# 0116-class-d-amp.net
KiCad netlist of a schematic drawn in EAGLE
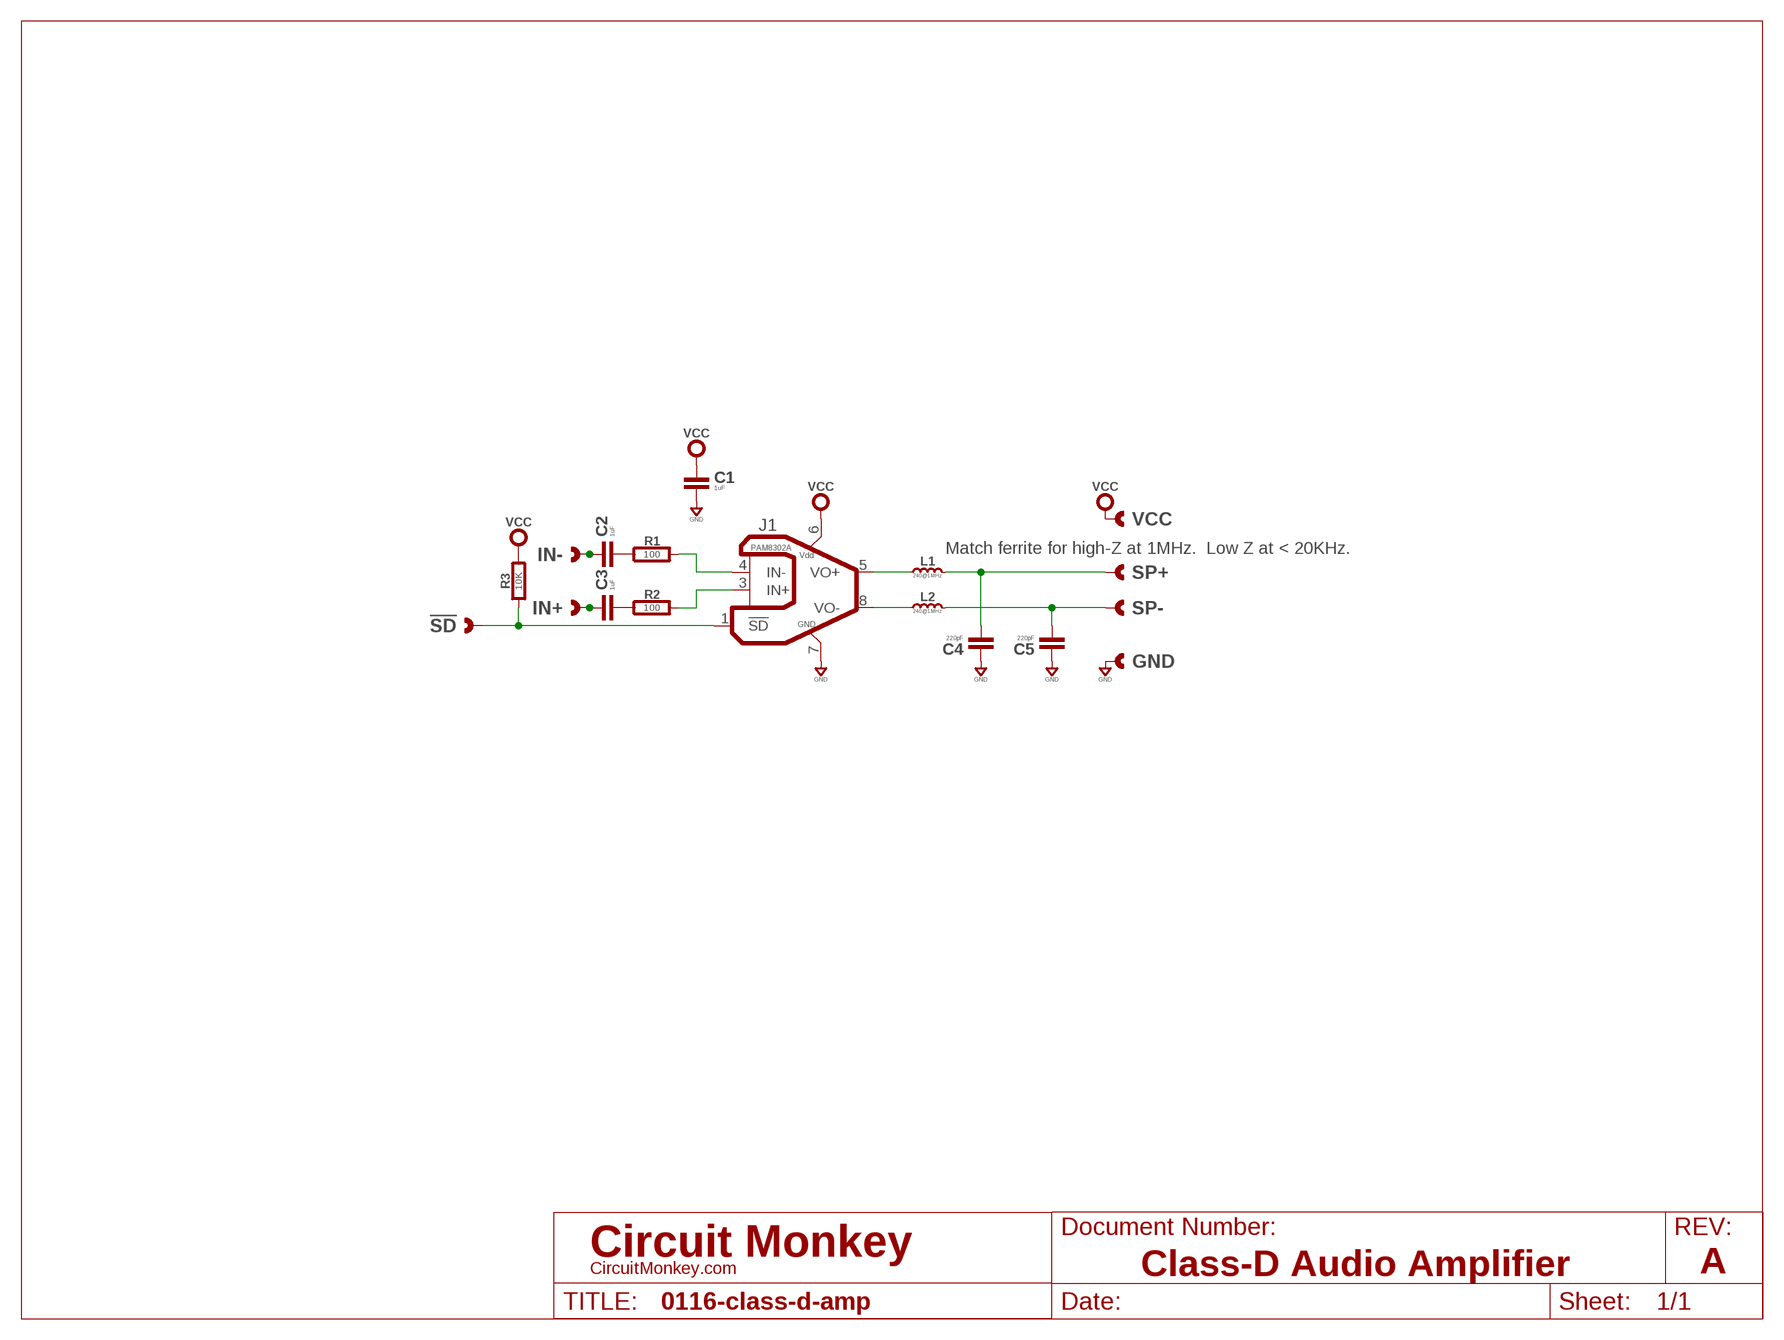
[diagram p0: schematic, sheet 1]

(export (version "E")
  (design (tool "Eeschema 10.0.6"))
  (components
    (comp (ref "!SD")
      (value "CAST-01X12.00MM")
      (footprint "eagle-import:CAST01-2.00MM")
      (libsource (lib "eagle-import") (part "CAST-01X12.00MM"))
    )
    (comp (ref "C1")
      (value "1uF")
      (footprint "eagle-import:0402-CAP")
      (libsource (lib "eagle-import") (part "CAPACITOR0402"))
    )
    (comp (ref "C2")
      (value "1uF")
      (footprint "eagle-import:0402-CAP")
      (libsource (lib "eagle-import") (part "CAPACITOR0402"))
    )
    (comp (ref "C3")
      (value "1uF")
      (footprint "eagle-import:0402-CAP")
      (libsource (lib "eagle-import") (part "CAPACITOR0402"))
    )
    (comp (ref "C4")
      (value "220pF")
      (footprint "eagle-import:0402-CAP")
      (libsource (lib "eagle-import") (part "CAPACITOR0402"))
    )
    (comp (ref "C5")
      (value "220pF")
      (footprint "eagle-import:0402-CAP")
      (libsource (lib "eagle-import") (part "CAPACITOR0402"))
    )
    (comp (ref "GND")
      (value "CAST-01X12.00MM")
      (footprint "eagle-import:CAST01-2.00MM")
      (libsource (lib "eagle-import") (part "CAST-01X12.00MM"))
    )
    (comp (ref "IN+")
      (value "CAST-01X12.00MM")
      (footprint "eagle-import:CAST01-2.00MM")
      (libsource (lib "eagle-import") (part "CAST-01X12.00MM"))
    )
    (comp (ref "IN-")
      (value "CAST-01X12.00MM")
      (footprint "eagle-import:CAST01-2.00MM")
      (libsource (lib "eagle-import") (part "CAST-01X12.00MM"))
    )
    (comp (ref "J1")
      (value "PAM8302A")
      (footprint "eagle-import:DFN-8-3X3")
      (fields (field (name "MFR") "Diodes, Inc.") (field (name "MPN") "PAM8302AAYC"))
      (libsource (lib "eagle-import") (part "PAM8302ADFN-3X3"))
    )
    (comp (ref "L1")
      (value "240@1MHz")
      (footprint "eagle-import:0402-IND")
      (fields (field (name "MFR") "TDK") (field (name "MPN") "MMZ1005S241HT000"))
      (libsource (lib "eagle-import") (part "FERRITE240OHM-600MA-0402"))
    )
    (comp (ref "L2")
      (value "240@1MHz")
      (footprint "eagle-import:0402-IND")
      (fields (field (name "MFR") "TDK") (field (name "MPN") "MMZ1005S241HT000"))
      (libsource (lib "eagle-import") (part "FERRITE240OHM-600MA-0402"))
    )
    (comp (ref "R1")
      (value "100")
      (footprint "eagle-import:0402-RES")
      (libsource (lib "eagle-import") (part "RESISTOR0402"))
    )
    (comp (ref "R2")
      (value "100")
      (footprint "eagle-import:0402-RES")
      (libsource (lib "eagle-import") (part "RESISTOR0402"))
    )
    (comp (ref "R3")
      (value "10K")
      (footprint "eagle-import:0402-RES")
      (libsource (lib "eagle-import") (part "RESISTOR0402"))
    )
    (comp (ref "SP+")
      (value "CAST-01X12.00MM")
      (footprint "eagle-import:CAST01-2.00MM")
      (libsource (lib "eagle-import") (part "CAST-01X12.00MM"))
    )
    (comp (ref "SP-")
      (value "CAST-01X12.00MM")
      (footprint "eagle-import:CAST01-2.00MM")
      (libsource (lib "eagle-import") (part "CAST-01X12.00MM"))
    )
    (comp (ref "VCC")
      (value "CAST-01X12.00MM")
      (footprint "eagle-import:CAST01-2.00MM")
      (libsource (lib "eagle-import") (part "CAST-01X12.00MM"))
    )
  )
  (nets
    (net (code "1") (name "GND") (class "Default")
      (node (ref "C1") (pin "2") (pinfunction "2_2") (pintype "passive"))
      (node (ref "C4") (pin "1") (pinfunction "1_1") (pintype "passive"))
      (node (ref "C5") (pin "1") (pinfunction "1_1") (pintype "passive"))
      (node (ref "GND") (pin "1") (pinfunction "1_1") (pintype "bidirectional"))
      (node (ref "GND") (pin "P$1") (pinfunction "1_P$1") (pintype "bidirectional"))
      (node (ref "GND") (pin "P$2") (pinfunction "1_P$2") (pintype "bidirectional"))
      (node (ref "J1") (pin "7") (pinfunction "GND_7") (pintype "bidirectional"))
    )
    (net (code "2") (name "Net-(C2-Pad1)") (class "Default")
      (node (ref "C2") (pin "1") (pinfunction "1_1") (pintype "passive"))
      (node (ref "IN-") (pin "1") (pinfunction "1_1") (pintype "bidirectional"))
      (node (ref "IN-") (pin "P$1") (pinfunction "1_P$1") (pintype "bidirectional"))
      (node (ref "IN-") (pin "P$2") (pinfunction "1_P$2") (pintype "bidirectional"))
    )
    (net (code "3") (name "Net-(C2-Pad2)") (class "Default")
      (node (ref "C2") (pin "2") (pinfunction "2_2") (pintype "passive"))
      (node (ref "R1") (pin "1") (pinfunction "1_1") (pintype "passive"))
    )
    (net (code "4") (name "Net-(C3-Pad1)") (class "Default")
      (node (ref "C3") (pin "1") (pinfunction "1_1") (pintype "passive"))
      (node (ref "IN+") (pin "1") (pinfunction "1_1") (pintype "bidirectional"))
      (node (ref "IN+") (pin "P$1") (pinfunction "1_P$1") (pintype "bidirectional"))
      (node (ref "IN+") (pin "P$2") (pinfunction "1_P$2") (pintype "bidirectional"))
    )
    (net (code "5") (name "Net-(C3-Pad2)") (class "Default")
      (node (ref "C3") (pin "2") (pinfunction "2_2") (pintype "passive"))
      (node (ref "R2") (pin "1") (pinfunction "1_1") (pintype "passive"))
    )
    (net (code "6") (name "Net-(J1-IN+)") (class "Default")
      (node (ref "J1") (pin "3") (pinfunction "IN+_3") (pintype "bidirectional"))
      (node (ref "R2") (pin "2") (pinfunction "2_2") (pintype "passive"))
    )
    (net (code "7") (name "Net-(J1-IN-)") (class "Default")
      (node (ref "J1") (pin "4") (pinfunction "IN-_4") (pintype "bidirectional"))
      (node (ref "R1") (pin "2") (pinfunction "2_2") (pintype "passive"))
    )
    (net (code "8") (name "Net-(J1-VO+)") (class "Default")
      (node (ref "J1") (pin "5") (pinfunction "VO+_5") (pintype "bidirectional"))
      (node (ref "L1") (pin "3") (pinfunction "1_3") (pintype "passive"))
    )
    (net (code "9") (name "Net-(J1-VO-)") (class "Default")
      (node (ref "J1") (pin "8") (pinfunction "VO-_8") (pintype "bidirectional"))
      (node (ref "L2") (pin "3") (pinfunction "1_3") (pintype "passive"))
    )
    (net (code "10") (name "Net-(J1-~{SD})") (class "Default")
      (node (ref "!SD") (pin "1") (pinfunction "1_1") (pintype "bidirectional"))
      (node (ref "!SD") (pin "P$1") (pinfunction "1_P$1") (pintype "bidirectional"))
      (node (ref "!SD") (pin "P$2") (pinfunction "1_P$2") (pintype "bidirectional"))
      (node (ref "J1") (pin "1") (pinfunction "~{SD}_1") (pintype "bidirectional"))
      (node (ref "R3") (pin "1") (pinfunction "1_1") (pintype "passive"))
    )
    (net (code "11") (name "Net-(L1-2)") (class "Default")
      (node (ref "C4") (pin "2") (pinfunction "2_2") (pintype "passive"))
      (node (ref "L1") (pin "4") (pinfunction "2_4") (pintype "passive"))
      (node (ref "SP+") (pin "1") (pinfunction "1_1") (pintype "bidirectional"))
      (node (ref "SP+") (pin "P$1") (pinfunction "1_P$1") (pintype "bidirectional"))
      (node (ref "SP+") (pin "P$2") (pinfunction "1_P$2") (pintype "bidirectional"))
    )
    (net (code "12") (name "Net-(L2-2)") (class "Default")
      (node (ref "C5") (pin "2") (pinfunction "2_2") (pintype "passive"))
      (node (ref "L2") (pin "4") (pinfunction "2_4") (pintype "passive"))
      (node (ref "SP-") (pin "1") (pinfunction "1_1") (pintype "bidirectional"))
      (node (ref "SP-") (pin "P$1") (pinfunction "1_P$1") (pintype "bidirectional"))
      (node (ref "SP-") (pin "P$2") (pinfunction "1_P$2") (pintype "bidirectional"))
    )
    (net (code "13") (name "VCC") (class "Default")
      (node (ref "C1") (pin "1") (pinfunction "1_1") (pintype "passive"))
      (node (ref "J1") (pin "6") (pinfunction "VDD_6") (pintype "bidirectional"))
      (node (ref "R3") (pin "2") (pinfunction "2_2") (pintype "passive"))
      (node (ref "VCC") (pin "1") (pinfunction "1_1") (pintype "bidirectional"))
      (node (ref "VCC") (pin "P$1") (pinfunction "1_P$1") (pintype "bidirectional"))
      (node (ref "VCC") (pin "P$2") (pinfunction "1_P$2") (pintype "bidirectional"))
    )
  )
)
